# Modem.net
KiCad netlist of a schematic drawn in Altium Designer
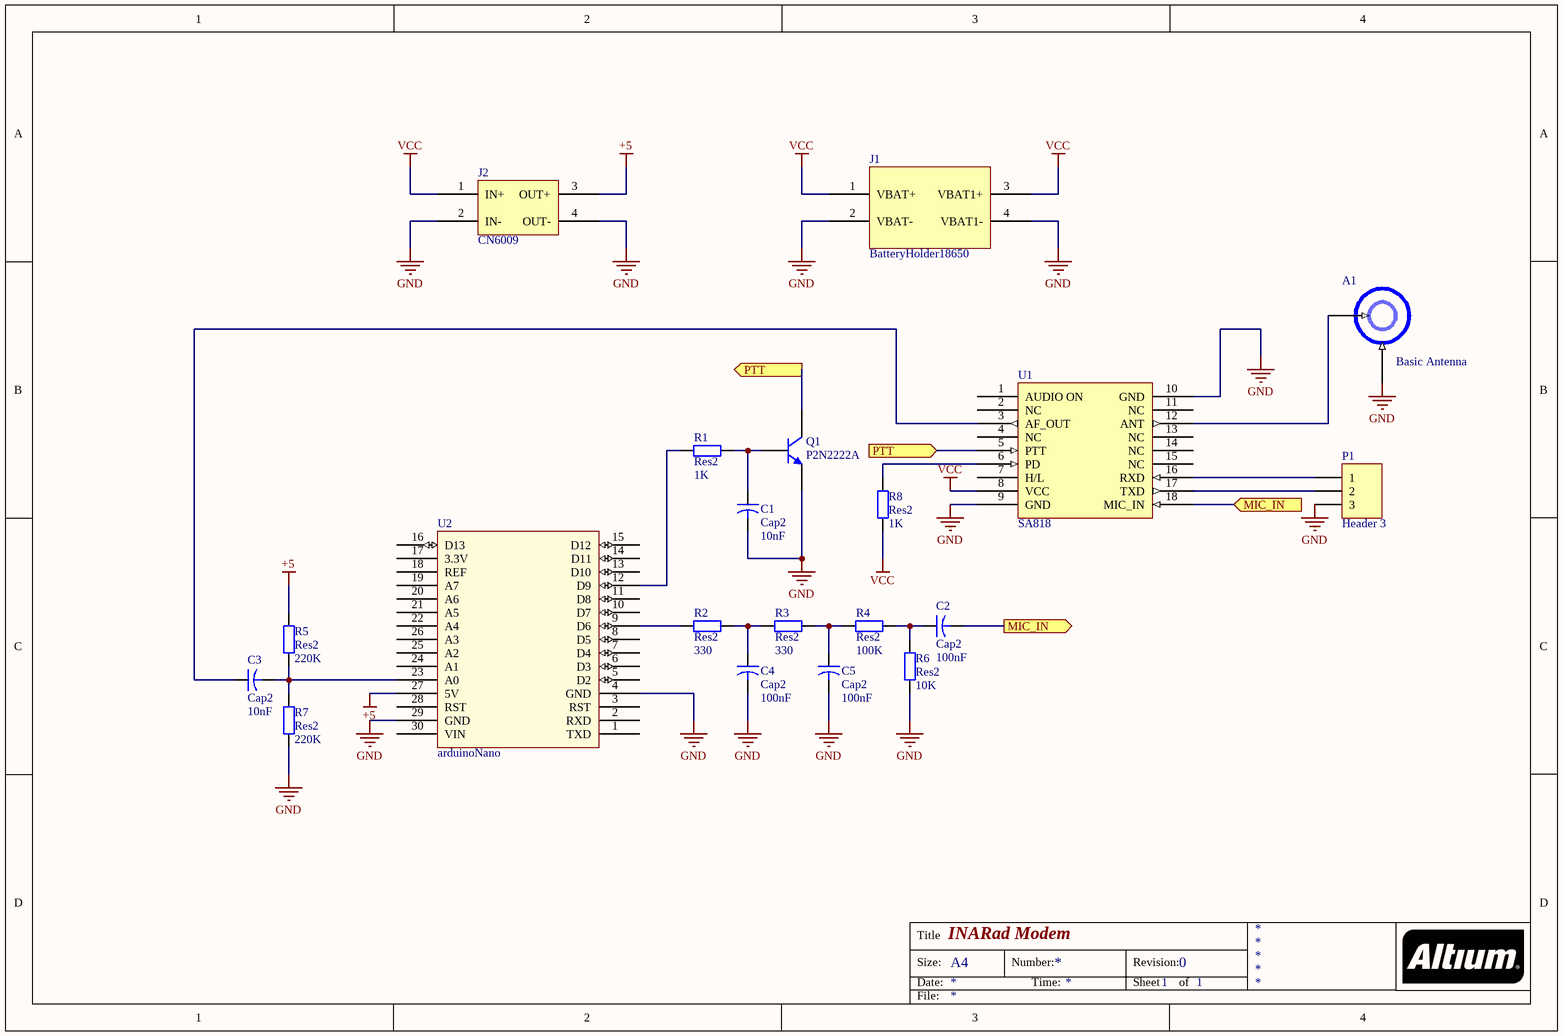
[diagram p0: Modem.SchDoc]

(export (version "E")
  (design (tool "Eeschema 10.0.6"))
  (components
    (comp (ref "A1")
      (value "Basic Antenna")
      (footprint "CON-SMA-EDGE062")
      (libsource (lib "Antenna") (part "Basic Antenna"))
    )
    (comp (ref "C1")
      (value "Cap2")
      (footprint "CAPR5-4X5")
      (description "Capacitor")
      (fields (field (name "ALTIUM_VALUE") "10nF") (field (name "PUBLISHER") "Altium Limited"))
      (libsource (lib "Miscellaneous Devices") (part "Cap2"))
    )
    (comp (ref "C2")
      (value "Cap2")
      (footprint "CAPR5-4X5")
      (description "Capacitor")
      (fields (field (name "ALTIUM_VALUE") "100nF") (field (name "PUBLISHER") "Altium Limited"))
      (libsource (lib "Miscellaneous Devices") (part "Cap2"))
    )
    (comp (ref "C3")
      (value "Cap2")
      (footprint "CAPR5-4X5")
      (description "Capacitor")
      (fields (field (name "ALTIUM_VALUE") "10nF") (field (name "PUBLISHER") "Altium Limited"))
      (libsource (lib "Miscellaneous Devices") (part "Cap2"))
    )
    (comp (ref "C4")
      (value "Cap2")
      (footprint "CAPR5-4X5")
      (description "Capacitor")
      (fields (field (name "ALTIUM_VALUE") "100nF") (field (name "PUBLISHER") "Altium Limited"))
      (libsource (lib "Miscellaneous Devices") (part "Cap2"))
    )
    (comp (ref "C5")
      (value "Cap2")
      (footprint "CAPR5-4X5")
      (description "Capacitor")
      (fields (field (name "ALTIUM_VALUE") "100nF") (field (name "PUBLISHER") "Altium Limited"))
      (libsource (lib "Miscellaneous Devices") (part "Cap2"))
    )
    (comp (ref "J1")
      (value "BatteryHolder18650")
      (footprint "BatteryHolder18650")
      (libsource (lib "BatteryHolder18650") (part "BatteryHolder18650"))
    )
    (comp (ref "J2")
      (value "CN6009")
      (footprint "CN6009")
      (libsource (lib "BoostConverterModules") (part "CN6009"))
    )
    (comp (ref "P1")
      (value "Header 3")
      (footprint "HDR1X3")
      (description "Header, 3-Pin")
      (fields (field (name "PUBLISHER") "Altium Limited"))
      (libsource (lib "Miscellaneous Connectors") (part "Header 3"))
    )
    (comp (ref "Q1")
      (value "P2N2222A")
      (footprint "29-04")
      (description "Amplifier Transistor NPN Silicon")
      (fields (field (name "PUBLISHER") "Altium Limited"))
      (libsource (lib "Motorola Discrete BJT") (part "P2N2222A"))
    )
    (comp (ref "R1")
      (value "Res2")
      (footprint "AXIAL-0.4")
      (description "Resistor")
      (fields (field (name "ALTIUM_VALUE") "1K") (field (name "PUBLISHER") "Altium Limited"))
      (libsource (lib "") (part "Res2_1"))
    )
    (comp (ref "R2")
      (value "Res2")
      (footprint "AXIAL-0.4")
      (description "Resistor")
      (fields (field (name "ALTIUM_VALUE") "330") (field (name "PUBLISHER") "Altium Limited"))
      (libsource (lib "") (part "Res2_1"))
    )
    (comp (ref "R3")
      (value "Res2")
      (footprint "AXIAL-0.4")
      (description "Resistor")
      (fields (field (name "ALTIUM_VALUE") "330") (field (name "PUBLISHER") "Altium Limited"))
      (libsource (lib "") (part "Res2_1"))
    )
    (comp (ref "R4")
      (value "Res2")
      (footprint "AXIAL-0.4")
      (description "Resistor")
      (fields (field (name "ALTIUM_VALUE") "100K") (field (name "PUBLISHER") "Altium Limited"))
      (libsource (lib "") (part "Res2_1"))
    )
    (comp (ref "R5")
      (value "Res2")
      (footprint "AXIAL-0.4")
      (description "Resistor")
      (fields (field (name "ALTIUM_VALUE") "220K") (field (name "PUBLISHER") "Altium Limited"))
      (libsource (lib "Miscellaneous Devices") (part "Res2"))
    )
    (comp (ref "R6")
      (value "Res2")
      (footprint "AXIAL-0.4")
      (description "Resistor")
      (fields (field (name "ALTIUM_VALUE") "10K") (field (name "PUBLISHER") "Altium Limited"))
      (libsource (lib "Miscellaneous Devices") (part "Res2"))
    )
    (comp (ref "R7")
      (value "Res2")
      (footprint "AXIAL-0.4")
      (description "Resistor")
      (fields (field (name "ALTIUM_VALUE") "220K") (field (name "PUBLISHER") "Altium Limited"))
      (libsource (lib "Miscellaneous Devices") (part "Res2"))
    )
    (comp (ref "R8")
      (value "Res2")
      (footprint "AXIAL-0.4")
      (description "Resistor")
      (fields (field (name "ALTIUM_VALUE") "1K") (field (name "PUBLISHER") "Altium Limited"))
      (libsource (lib "Miscellaneous Devices") (part "Res2"))
    )
    (comp (ref "U1") (value "SA818") (footprint "SA818") (libsource (lib "SA818") (part "SA818")))
    (comp (ref "U2")
      (value "arduinoNano")
      (footprint "Arduino nano")
      (libsource (lib "arduinoNano") (part "arduinoNano"))
    )
  )
  (nets
    (net (code "1") (name "+5") (class "Default")
      (node (ref "J2") (pin "3") (pinfunction "OUT+_3") (pintype "power_in"))
      (node (ref "R5") (pin "2") (pinfunction "2_2") (pintype "passive"))
      (node (ref "U2") (pin "27") (pinfunction "5V_27") (pintype "power_in"))
    )
    (net (code "2") (name "/MIC_IN") (class "Default")
      (node (ref "C2") (pin "2") (pinfunction "2_2") (pintype "passive"))
      (node (ref "U1") (pin "18") (pinfunction "MIC_IN_18") (pintype "input"))
    )
    (net (code "3") (name "/PTT") (class "Default")
      (node (ref "Q1") (pin "1") (pinfunction "C_1") (pintype "passive"))
      (node (ref "U1") (pin "5") (pinfunction "PTT_5") (pintype "input"))
    )
    (net (code "4") (name "GND") (class "Default")
      (node (ref "A1") (pin "G") (pinfunction "Ground_G") (pintype "input"))
      (node (ref "C1") (pin "2") (pinfunction "2_2") (pintype "passive"))
      (node (ref "C4") (pin "2") (pinfunction "2_2") (pintype "passive"))
      (node (ref "C5") (pin "2") (pinfunction "2_2") (pintype "passive"))
      (node (ref "J1") (pin "2") (pinfunction "VBAT-_2") (pintype "passive"))
      (node (ref "J1") (pin "4") (pinfunction "VBAT1-_4") (pintype "passive"))
      (node (ref "J2") (pin "2") (pinfunction "IN-_2") (pintype "power_in"))
      (node (ref "J2") (pin "4") (pinfunction "OUT-_4") (pintype "power_in"))
      (node (ref "P1") (pin "3") (pinfunction "3_3") (pintype "passive"))
      (node (ref "Q1") (pin "3") (pinfunction "E_3") (pintype "passive"))
      (node (ref "R6") (pin "1") (pinfunction "1_1") (pintype "passive"))
      (node (ref "R7") (pin "1") (pinfunction "1_1") (pintype "passive"))
      (node (ref "U1") (pin "10") (pinfunction "GND_10") (pintype "power_in"))
      (node (ref "U1") (pin "9") (pinfunction "GND_9") (pintype "power_in"))
      (node (ref "U2") (pin "29") (pinfunction "GND_29") (pintype "power_in"))
      (node (ref "U2") (pin "4") (pinfunction "GND_4") (pintype "power_in"))
    )
    (net (code "5") (name "Net-(A1-Signal)") (class "Default")
      (node (ref "A1") (pin "S") (pinfunction "Signal_S") (pintype "input"))
      (node (ref "U1") (pin "12") (pinfunction "ANT_12") (pintype "output"))
    )
    (net (code "6") (name "Net-(C2-Pad1)") (class "Default")
      (node (ref "C2") (pin "1") (pinfunction "1_1") (pintype "passive"))
      (node (ref "R4") (pin "2") (pinfunction "2_2") (pintype "passive"))
      (node (ref "R6") (pin "2") (pinfunction "2_2") (pintype "passive"))
    )
    (net (code "7") (name "Net-(C4-Pad1)") (class "Default")
      (node (ref "C4") (pin "1") (pinfunction "1_1") (pintype "passive"))
      (node (ref "R2") (pin "2") (pinfunction "2_2") (pintype "passive"))
      (node (ref "R3") (pin "1") (pinfunction "1_1") (pintype "passive"))
    )
    (net (code "8") (name "Net-(C5-Pad1)") (class "Default")
      (node (ref "C5") (pin "1") (pinfunction "1_1") (pintype "passive"))
      (node (ref "R3") (pin "2") (pinfunction "2_2") (pintype "passive"))
      (node (ref "R4") (pin "1") (pinfunction "1_1") (pintype "passive"))
    )
    (net (code "9") (name "Net-(Q1-B)") (class "Default")
      (node (ref "C1") (pin "1") (pinfunction "1_1") (pintype "passive"))
      (node (ref "Q1") (pin "2") (pinfunction "B_2") (pintype "passive"))
      (node (ref "R1") (pin "2") (pinfunction "2_2") (pintype "passive"))
    )
    (net (code "10") (name "Net-(U1-AF_OUT)") (class "Default")
      (node (ref "C3") (pin "1") (pinfunction "1_1") (pintype "passive"))
      (node (ref "U1") (pin "3") (pinfunction "AF_OUT_3") (pintype "output"))
    )
    (net (code "11") (name "Net-(U1-PD)") (class "Default")
      (node (ref "R8") (pin "2") (pinfunction "2_2") (pintype "passive"))
      (node (ref "U1") (pin "6") (pinfunction "PD_6") (pintype "input"))
    )
    (net (code "12") (name "Net-(U1-RXD)") (class "Default")
      (node (ref "P1") (pin "1") (pinfunction "1_1") (pintype "passive"))
      (node (ref "U1") (pin "16") (pinfunction "RXD_16") (pintype "input"))
    )
    (net (code "13") (name "Net-(U1-TXD)") (class "Default")
      (node (ref "P1") (pin "2") (pinfunction "2_2") (pintype "passive"))
      (node (ref "U1") (pin "17") (pinfunction "TXD_17") (pintype "output"))
    )
    (net (code "14") (name "Net-(U2-A0)") (class "Default")
      (node (ref "C3") (pin "2") (pinfunction "2_2") (pintype "passive"))
      (node (ref "R5") (pin "1") (pinfunction "1_1") (pintype "passive"))
      (node (ref "R7") (pin "2") (pinfunction "2_2") (pintype "passive"))
      (node (ref "U2") (pin "23") (pinfunction "A0_23") (pintype "passive"))
    )
    (net (code "15") (name "Net-(U2-D6)") (class "Default")
      (node (ref "R2") (pin "1") (pinfunction "1_1") (pintype "passive"))
      (node (ref "U2") (pin "9") (pinfunction "D6_9") (pintype "bidirectional"))
    )
    (net (code "16") (name "Net-(U2-D9)") (class "Default")
      (node (ref "R1") (pin "1") (pinfunction "1_1") (pintype "passive"))
      (node (ref "U2") (pin "12") (pinfunction "D9_12") (pintype "bidirectional"))
    )
    (net (code "17") (name "VCC") (class "Default")
      (node (ref "J1") (pin "1") (pinfunction "VBAT+_1") (pintype "passive"))
      (node (ref "J1") (pin "3") (pinfunction "VBAT1+_3") (pintype "passive"))
      (node (ref "J2") (pin "1") (pinfunction "IN+_1") (pintype "power_in"))
      (node (ref "R8") (pin "1") (pinfunction "1_1") (pintype "passive"))
      (node (ref "U1") (pin "8") (pinfunction "VCC_8") (pintype "power_in"))
    )
    (net (code "18") (name "unconnected-(U1-AUDIO_ON-Pad1)") (class "Default")
      (node (ref "U1") (pin "1") (pinfunction "AUDIO_ON_1") (pintype "passive"))
    )
    (net (code "19") (name "unconnected-(U1-H{slash}L-Pad7)") (class "Default")
      (node (ref "U1") (pin "7") (pinfunction "H/L_7") (pintype "tri_state"))
    )
    (net (code "20") (name "unconnected-(U1-NC-Pad2)") (class "Default")
      (node (ref "U1") (pin "2") (pinfunction "NC_2") (pintype "passive"))
    )
    (net (code "21") (name "unconnected-(U1-NC-Pad4)") (class "Default")
      (node (ref "U1") (pin "4") (pinfunction "NC_4") (pintype "passive"))
    )
    (net (code "22") (name "unconnected-(U1-NC-Pad11)") (class "Default")
      (node (ref "U1") (pin "11") (pinfunction "NC_11") (pintype "passive"))
    )
    (net (code "23") (name "unconnected-(U1-NC-Pad13)") (class "Default")
      (node (ref "U1") (pin "13") (pinfunction "NC_13") (pintype "passive"))
    )
    (net (code "24") (name "unconnected-(U1-NC-Pad14)") (class "Default")
      (node (ref "U1") (pin "14") (pinfunction "NC_14") (pintype "passive"))
    )
    (net (code "25") (name "unconnected-(U1-NC-Pad15)") (class "Default")
      (node (ref "U1") (pin "15") (pinfunction "NC_15") (pintype "passive"))
    )
    (net (code "26") (name "unconnected-(U2-3.3V-Pad17)") (class "Default")
      (node (ref "U2") (pin "17") (pinfunction "3.3V_17") (pintype "power_in"))
    )
    (net (code "27") (name "unconnected-(U2-A1-Pad24)") (class "Default")
      (node (ref "U2") (pin "24") (pinfunction "A1_24") (pintype "passive"))
    )
    (net (code "28") (name "unconnected-(U2-A2-Pad25)") (class "Default")
      (node (ref "U2") (pin "25") (pinfunction "A2_25") (pintype "passive"))
    )
    (net (code "29") (name "unconnected-(U2-A3-Pad26)") (class "Default")
      (node (ref "U2") (pin "26") (pinfunction "A3_26") (pintype "passive"))
    )
    (net (code "30") (name "unconnected-(U2-A4-Pad22)") (class "Default")
      (node (ref "U2") (pin "22") (pinfunction "A4_22") (pintype "passive"))
    )
    (net (code "31") (name "unconnected-(U2-A5-Pad21)") (class "Default")
      (node (ref "U2") (pin "21") (pinfunction "A5_21") (pintype "passive"))
    )
    (net (code "32") (name "unconnected-(U2-A6-Pad20)") (class "Default")
      (node (ref "U2") (pin "20") (pinfunction "A6_20") (pintype "passive"))
    )
    (net (code "33") (name "unconnected-(U2-A7-Pad19)") (class "Default")
      (node (ref "U2") (pin "19") (pinfunction "A7_19") (pintype "passive"))
    )
    (net (code "34") (name "unconnected-(U2-D2-Pad5)") (class "Default")
      (node (ref "U2") (pin "5") (pinfunction "D2_5") (pintype "bidirectional"))
    )
    (net (code "35") (name "unconnected-(U2-D3-Pad6)") (class "Default")
      (node (ref "U2") (pin "6") (pinfunction "D3_6") (pintype "bidirectional"))
    )
    (net (code "36") (name "unconnected-(U2-D4-Pad7)") (class "Default")
      (node (ref "U2") (pin "7") (pinfunction "D4_7") (pintype "bidirectional"))
    )
    (net (code "37") (name "unconnected-(U2-D5-Pad8)") (class "Default")
      (node (ref "U2") (pin "8") (pinfunction "D5_8") (pintype "bidirectional"))
    )
    (net (code "38") (name "unconnected-(U2-D7-Pad10)") (class "Default")
      (node (ref "U2") (pin "10") (pinfunction "D7_10") (pintype "bidirectional"))
    )
    (net (code "39") (name "unconnected-(U2-D8-Pad11)") (class "Default")
      (node (ref "U2") (pin "11") (pinfunction "D8_11") (pintype "bidirectional"))
    )
    (net (code "40") (name "unconnected-(U2-D10-Pad13)") (class "Default")
      (node (ref "U2") (pin "13") (pinfunction "D10_13") (pintype "bidirectional"))
    )
    (net (code "41") (name "unconnected-(U2-D11-Pad14)") (class "Default")
      (node (ref "U2") (pin "14") (pinfunction "D11_14") (pintype "bidirectional"))
    )
    (net (code "42") (name "unconnected-(U2-D12-Pad15)") (class "Default")
      (node (ref "U2") (pin "15") (pinfunction "D12_15") (pintype "bidirectional"))
    )
    (net (code "43") (name "unconnected-(U2-D13-Pad16)") (class "Default")
      (node (ref "U2") (pin "16") (pinfunction "D13_16") (pintype "bidirectional"))
    )
    (net (code "44") (name "unconnected-(U2-REF-Pad18)") (class "Default")
      (node (ref "U2") (pin "18") (pinfunction "REF_18") (pintype "passive"))
    )
    (net (code "45") (name "unconnected-(U2-RST-Pad3)") (class "Default")
      (node (ref "U2") (pin "3") (pinfunction "RST_3") (pintype "passive"))
    )
    (net (code "46") (name "unconnected-(U2-RST-Pad28)") (class "Default")
      (node (ref "U2") (pin "28") (pinfunction "RST_28") (pintype "passive"))
    )
    (net (code "47") (name "unconnected-(U2-RXD-Pad2)") (class "Default")
      (node (ref "U2") (pin "2") (pinfunction "RXD_2") (pintype "passive"))
    )
    (net (code "48") (name "unconnected-(U2-TXD-Pad1)") (class "Default")
      (node (ref "U2") (pin "1") (pinfunction "TXD_1") (pintype "passive"))
    )
    (net (code "49") (name "unconnected-(U2-VIN-Pad30)") (class "Default")
      (node (ref "U2") (pin "30") (pinfunction "VIN_30") (pintype "power_in"))
    )
  )
)
